# PhotoResistor.net
KiCad netlist of a schematic drawn in EAGLE
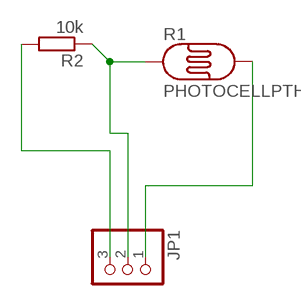
[diagram p0: schematic, sheet 1]

(export (version "E")
  (design (tool "Eeschema 10.0.6"))
  (components
    (comp (ref "JP1")
      (value "PINHD-1X3/90")
      (footprint "eagle-import:1X03_90")
      (libsource (lib "eagle-import") (part "PINHD-1X3/90"))
    )
    (comp (ref "R1")
      (value "PHOTOCELLPTH")
      (footprint "eagle-import:PHOTOCELL")
      (libsource (lib "eagle-import") (part "PHOTOCELLPTH"))
    )
    (comp (ref "R2")
      (value "10k")
      (footprint "eagle-import:0207_7")
      (libsource (lib "eagle-import") (part "R-EU_0207/7"))
    )
  )
  (nets
    (net (code "1") (name "Net-(JP1-Pad3)") (class "Default")
      (node (ref "JP1") (pin "3") (pinfunction "3_3") (pintype "passive"))
      (node (ref "R2") (pin "2") (pinfunction "2_2") (pintype "passive"))
    )
    (net (code "2") (name "Net-(R1-P$1)") (class "Default")
      (node (ref "JP1") (pin "2") (pinfunction "2_2") (pintype "passive"))
      (node (ref "R1") (pin "1") (pinfunction "P$1_1") (pintype "bidirectional"))
      (node (ref "R2") (pin "1") (pinfunction "1_1") (pintype "passive"))
    )
    (net (code "3") (name "Net-(R1-P$2)") (class "Default")
      (node (ref "JP1") (pin "1") (pinfunction "1_1") (pintype "passive"))
      (node (ref "R1") (pin "2") (pinfunction "P$2_2") (pintype "bidirectional"))
    )
  )
)
